# dasblinkenhat-controller-mk-3_2.net
KiCad netlist of a schematic drawn in EAGLE
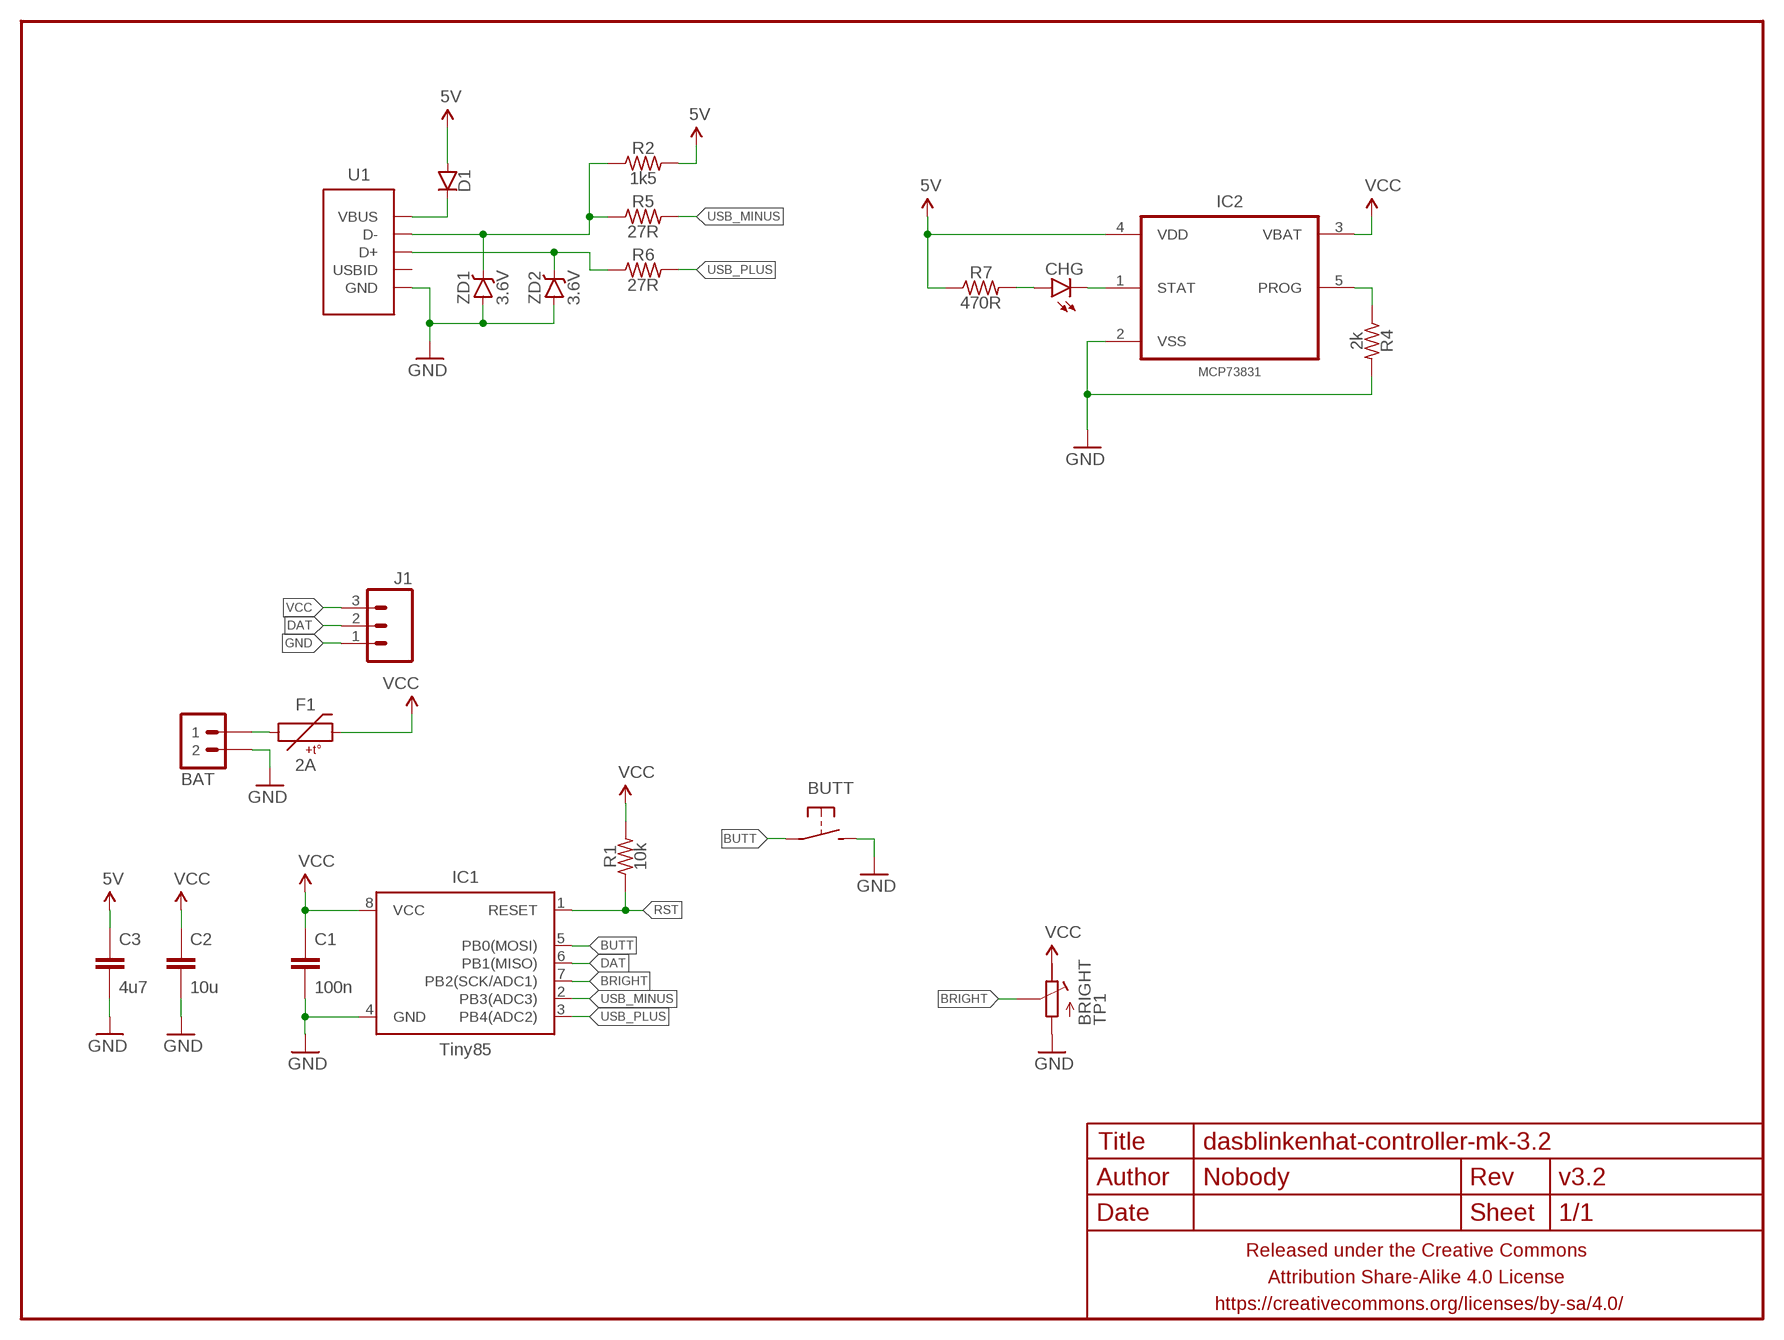
[diagram p0: schematic, sheet 1]

(export (version "E")
  (design (tool "Eeschema 10.0.6"))
  (components
    (comp (ref "BAT")
      (value "M02JST-2MM-SMT")
      (footprint "eagle-import:JST-2-SMD")
      (libsource (lib "eagle-import") (part "M02JST-2MM-SMT"))
    )
    (comp (ref "BUTT")
      (value "DTS-6MM")
      (footprint "eagle-import:DTSM-6")
      (libsource (lib "eagle-import") (part "SPST-NO-TACT6MM-SMD"))
    )
    (comp (ref "C1")
      (value "100n")
      (footprint "eagle-import:C0603")
      (libsource (lib "eagle-import") (part "CAPACITOR-CERAMICC0603"))
    )
    (comp (ref "C2")
      (value "10u")
      (footprint "eagle-import:C0805")
      (libsource (lib "eagle-import") (part "CAPACITOR-CERAMICC0805"))
    )
    (comp (ref "C3")
      (value "4u7")
      (footprint "eagle-import:C0805")
      (libsource (lib "eagle-import") (part "a_parts_CAPACITOR-CERAMICC0805"))
    )
    (comp (ref "CHG")
      (value "LED0603")
      (footprint "eagle-import:LED-0603")
      (libsource (lib "eagle-import") (part "LED0603"))
    )
    (comp (ref "D1")
      (value "DIODESOD123")
      (footprint "eagle-import:SOD123")
      (libsource (lib "eagle-import") (part "DIODESOD123"))
    )
    (comp (ref "F1")
      (value "2A")
      (footprint "eagle-import:PTC-1206")
      (libsource (lib "eagle-import") (part "PTCSMD"))
    )
    (comp (ref "FRAME1")
      (value "FRAME-LETTERNO_PACKAGE")
      (footprint "eagle-import:DUMMY")
      (fields (field (name "VERSION") "v3.2") (field (name "DESIGNER") "Nobody"))
      (libsource (lib "eagle-import") (part "FRAME-LETTERNO_PACKAGE"))
    )
    (comp (ref "IC1")
      (value "Tiny85")
      (footprint "eagle-import:SO08-EIAJ")
      (libsource (lib "eagle-import") (part "ATTINY45TINY85-20-SOICW"))
    )
    (comp (ref "IC2")
      (value "MCP73831")
      (footprint "eagle-import:SOT95P280X145-5N")
      (fields (field (name "MPN") "MCP73831T-2ACI/OT"))
      (libsource (lib "eagle-import") (part "MCP73831T-2ACI/OT"))
    )
    (comp (ref "J1")
      (value "M03JST-XH-RA-PTH")
      (footprint "eagle-import:JST-3-XH-RA-PTH")
      (libsource (lib "eagle-import") (part "M03JST-XH-RA-PTH"))
    )
    (comp (ref "R1")
      (value "10k")
      (footprint "eagle-import:R0603")
      (libsource (lib "eagle-import") (part "RESISTORR0603"))
    )
    (comp (ref "R2")
      (value "1k5")
      (footprint "eagle-import:R0603")
      (libsource (lib "eagle-import") (part "RESISTORR0603"))
    )
    (comp (ref "R4")
      (value "2k")
      (footprint "eagle-import:R0603")
      (libsource (lib "eagle-import") (part "RESISTORR0603"))
    )
    (comp (ref "R5")
      (value "27R")
      (footprint "eagle-import:R0603")
      (libsource (lib "eagle-import") (part "RESISTORR0603"))
    )
    (comp (ref "R6")
      (value "27R")
      (footprint "eagle-import:R0603")
      (libsource (lib "eagle-import") (part "RESISTORR0603"))
    )
    (comp (ref "R7")
      (value "470R")
      (footprint "eagle-import:R0603")
      (libsource (lib "eagle-import") (part "RESISTORR0603"))
    )
    (comp (ref "TP1")
      (value "BRIGHT")
      (footprint "eagle-import:EVM3Y")
      (libsource (lib "eagle-import") (part "POTENTIOMETEREVM3Y"))
    )
    (comp (ref "U1")
      (value "USB-ABFCI-10103594-USB-MICRO-B-LESS")
      (footprint "eagle-import:FCI-10103594-USB-MICRO-B-LESS")
      (libsource (lib "eagle-import") (part "USB-ABFCI-10103594-USB-MICRO-B-LESS"))
    )
    (comp (ref "ZD1")
      (value "3.6V")
      (footprint "eagle-import:SOD323-ZENNER")
      (libsource (lib "eagle-import") (part "DIODE-ZENERSOD323"))
    )
    (comp (ref "ZD2")
      (value "3.6V")
      (footprint "eagle-import:SOD323-ZENNER")
      (libsource (lib "eagle-import") (part "DIODE-ZENERSOD323"))
    )
  )
  (nets
    (net (code "1") (name "5V") (class "Default")
      (node (ref "C3") (pin "1") (pinfunction "1_1") (pintype "passive"))
      (node (ref "D1") (pin "A") (pinfunction "A_A") (pintype "passive"))
      (node (ref "IC2") (pin "4") (pinfunction "VDD_4") (pintype "power_in"))
      (node (ref "R2") (pin "2") (pinfunction "2_2") (pintype "passive"))
      (node (ref "R7") (pin "1") (pinfunction "1_1") (pintype "passive"))
    )
    (net (code "2") (name "BRIGHT") (class "Default")
      (node (ref "IC1") (pin "7") (pinfunction "PB2(SCK/ADC1)_7") (pintype "bidirectional"))
      (node (ref "TP1") (pin "S") (pinfunction "S_S") (pintype "passive"))
    )
    (net (code "3") (name "BUTT") (class "Default")
      (node (ref "BUTT") (pin "1") (pinfunction "1_1") (pintype "passive"))
      (node (ref "BUTT") (pin "2") (pinfunction "1_2") (pintype "passive"))
      (node (ref "IC1") (pin "5") (pinfunction "PB0(MOSI)_5") (pintype "bidirectional"))
    )
    (net (code "4") (name "DAT") (class "Default")
      (node (ref "IC1") (pin "6") (pinfunction "PB1(MISO)_6") (pintype "bidirectional"))
      (node (ref "J1") (pin "2") (pinfunction "2_2") (pintype "passive"))
    )
    (net (code "5") (name "GND") (class "Default")
      (node (ref "BAT") (pin "1") (pinfunction "2_1") (pintype "passive"))
      (node (ref "BUTT") (pin "3") (pinfunction "2_3") (pintype "passive"))
      (node (ref "BUTT") (pin "4") (pinfunction "2_4") (pintype "passive"))
      (node (ref "C1") (pin "2") (pinfunction "2_2") (pintype "passive"))
      (node (ref "C2") (pin "2") (pinfunction "2_2") (pintype "passive"))
      (node (ref "C3") (pin "2") (pinfunction "2_2") (pintype "passive"))
      (node (ref "IC1") (pin "4") (pinfunction "GND_4") (pintype "bidirectional"))
      (node (ref "IC2") (pin "2") (pinfunction "VSS_2") (pintype "power_in"))
      (node (ref "J1") (pin "1") (pinfunction "1_1") (pintype "passive"))
      (node (ref "R4") (pin "2") (pinfunction "2_2") (pintype "passive"))
      (node (ref "TP1") (pin "A") (pinfunction "A_A") (pintype "passive"))
      (node (ref "U1") (pin "5") (pinfunction "GND_5") (pintype "bidirectional"))
      (node (ref "ZD1") (pin "A") (pinfunction "A_A") (pintype "passive"))
      (node (ref "ZD2") (pin "A") (pinfunction "A_A") (pintype "passive"))
    )
    (net (code "6") (name "Net-(BAT-1)") (class "Default")
      (node (ref "BAT") (pin "2") (pinfunction "1_2") (pintype "passive"))
      (node (ref "F1") (pin "1") (pinfunction "1_1") (pintype "passive"))
    )
    (net (code "7") (name "Net-(CHG-PadA)") (class "Default")
      (node (ref "CHG") (pin "A") (pinfunction "A_A") (pintype "passive"))
      (node (ref "R7") (pin "2") (pinfunction "2_2") (pintype "passive"))
    )
    (net (code "8") (name "Net-(IC2-PROG)") (class "Default")
      (node (ref "IC2") (pin "5") (pinfunction "PROG_5") (pintype "input"))
      (node (ref "R4") (pin "1") (pinfunction "1_1") (pintype "passive"))
    )
    (net (code "9") (name "Net-(IC2-STAT)") (class "Default")
      (node (ref "CHG") (pin "C") (pinfunction "C_C") (pintype "passive"))
      (node (ref "IC2") (pin "1") (pinfunction "STAT_1") (pintype "output"))
    )
    (net (code "10") (name "Net-(U1-D+)") (class "Default")
      (node (ref "R6") (pin "1") (pinfunction "1_1") (pintype "passive"))
      (node (ref "U1") (pin "3") (pinfunction "D+_3") (pintype "bidirectional"))
      (node (ref "ZD2") (pin "C") (pinfunction "C_C") (pintype "passive"))
    )
    (net (code "11") (name "Net-(U1-D-)") (class "Default")
      (node (ref "R2") (pin "1") (pinfunction "1_1") (pintype "passive"))
      (node (ref "R5") (pin "1") (pinfunction "1_1") (pintype "passive"))
      (node (ref "U1") (pin "2") (pinfunction "D-_2") (pintype "bidirectional"))
      (node (ref "ZD1") (pin "C") (pinfunction "C_C") (pintype "passive"))
    )
    (net (code "12") (name "Net-(U1-VBUS)") (class "Default")
      (node (ref "D1") (pin "C") (pinfunction "C_C") (pintype "passive"))
      (node (ref "U1") (pin "1") (pinfunction "VBUS_1") (pintype "bidirectional"))
    )
    (net (code "13") (name "RST") (class "Default")
      (node (ref "IC1") (pin "1") (pinfunction "RESET_1") (pintype "bidirectional"))
      (node (ref "R1") (pin "1") (pinfunction "1_1") (pintype "passive"))
    )
    (net (code "14") (name "USB_MINUS") (class "Default")
      (node (ref "IC1") (pin "2") (pinfunction "PB3(ADC3)_2") (pintype "bidirectional"))
      (node (ref "R5") (pin "2") (pinfunction "2_2") (pintype "passive"))
    )
    (net (code "15") (name "USB_PLUS") (class "Default")
      (node (ref "IC1") (pin "3") (pinfunction "PB4(ADC2)_3") (pintype "bidirectional"))
      (node (ref "R6") (pin "2") (pinfunction "2_2") (pintype "passive"))
    )
    (net (code "16") (name "VCC") (class "Default")
      (node (ref "C1") (pin "1") (pinfunction "1_1") (pintype "passive"))
      (node (ref "C2") (pin "1") (pinfunction "1_1") (pintype "passive"))
      (node (ref "F1") (pin "2") (pinfunction "2_2") (pintype "passive"))
      (node (ref "IC1") (pin "8") (pinfunction "VCC_8") (pintype "bidirectional"))
      (node (ref "IC2") (pin "3") (pinfunction "VBAT_3") (pintype "output"))
      (node (ref "J1") (pin "3") (pinfunction "3_3") (pintype "passive"))
      (node (ref "R1") (pin "2") (pinfunction "2_2") (pintype "passive"))
      (node (ref "TP1") (pin "E") (pinfunction "E_E") (pintype "passive"))
    )
    (net (code "17") (name "unconnected-(U1-USBID-Pad4)") (class "Default")
      (node (ref "U1") (pin "4") (pinfunction "USBID_4") (pintype "bidirectional"))
    )
  )
)
